# RMP_LED_MODULE.net
KiCad netlist of a schematic drawn in Altium Designer
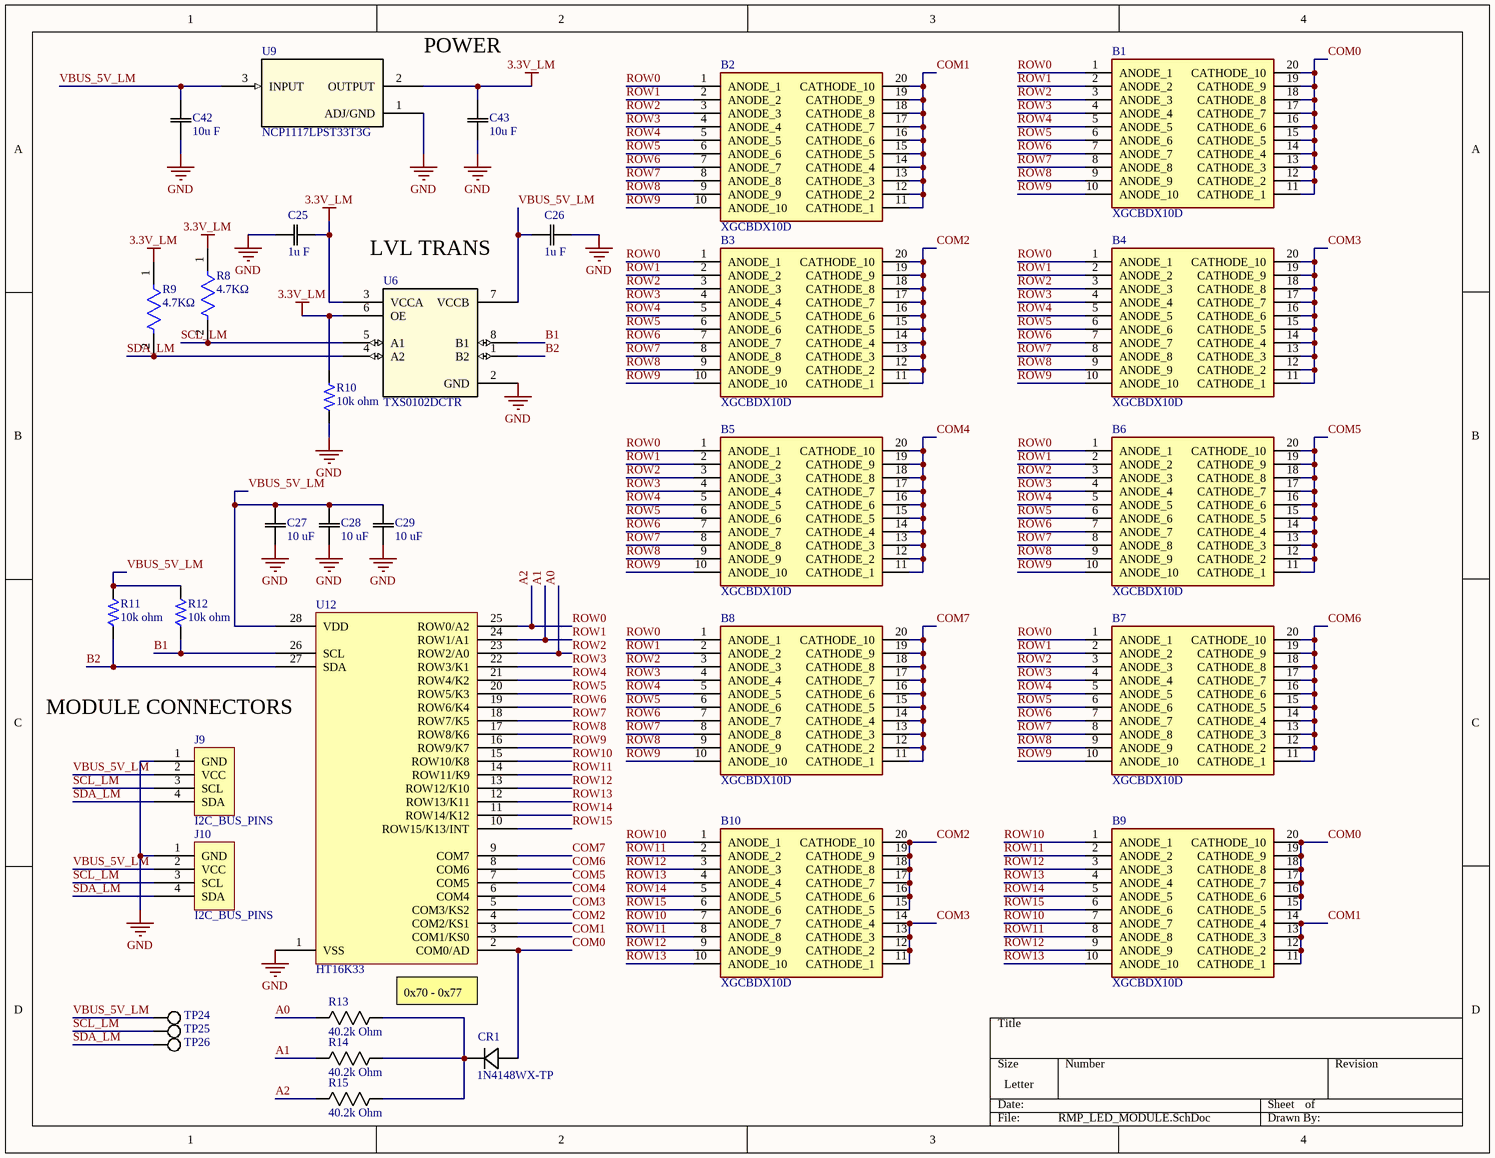
[diagram p0: RMP_LED_MODULE.SchDoc]

(export (version "E")
  (design (tool "Eeschema 10.0.6"))
  (components
    (comp (ref "B1")
      (value "XGCBDX10D")
      (footprint "DIPS750W75P254L2540H825Q20N")
      (description "BARGRAPH 10-SEGMENT BLUE")
      (libsource (lib "Schlib1") (part "XGCBDX10D"))
    )
    (comp (ref "B2")
      (value "XGCBDX10D")
      (footprint "DIPS750W75P254L2540H825Q20N")
      (description "BARGRAPH 10-SEGMENT BLUE")
      (libsource (lib "Schlib1") (part "XGCBDX10D"))
    )
    (comp (ref "B3")
      (value "XGCBDX10D")
      (footprint "DIPS750W75P254L2540H825Q20N")
      (description "BARGRAPH 10-SEGMENT BLUE")
      (libsource (lib "Schlib1") (part "XGCBDX10D"))
    )
    (comp (ref "B4")
      (value "XGCBDX10D")
      (footprint "DIPS750W75P254L2540H825Q20N")
      (description "BARGRAPH 10-SEGMENT BLUE")
      (libsource (lib "Schlib1") (part "XGCBDX10D"))
    )
    (comp (ref "B5")
      (value "XGCBDX10D")
      (footprint "DIPS750W75P254L2540H825Q20N")
      (description "BARGRAPH 10-SEGMENT BLUE")
      (libsource (lib "Schlib1") (part "XGCBDX10D"))
    )
    (comp (ref "B6")
      (value "XGCBDX10D")
      (footprint "DIPS750W75P254L2540H825Q20N")
      (description "BARGRAPH 10-SEGMENT BLUE")
      (libsource (lib "Schlib1") (part "XGCBDX10D"))
    )
    (comp (ref "B7")
      (value "XGCBDX10D")
      (footprint "DIPS750W75P254L2540H825Q20N")
      (description "BARGRAPH 10-SEGMENT BLUE")
      (libsource (lib "Schlib1") (part "XGCBDX10D"))
    )
    (comp (ref "B8")
      (value "XGCBDX10D")
      (footprint "DIPS750W75P254L2540H825Q20N")
      (description "BARGRAPH 10-SEGMENT BLUE")
      (libsource (lib "Schlib1") (part "XGCBDX10D"))
    )
    (comp (ref "B9")
      (value "XGCBDX10D")
      (footprint "DIPS750W75P254L2540H825Q20N")
      (description "BARGRAPH 10-SEGMENT BLUE")
      (libsource (lib "Schlib1") (part "XGCBDX10D"))
    )
    (comp (ref "B10")
      (value "XGCBDX10D")
      (footprint "DIPS750W75P254L2540H825Q20N")
      (description "BARGRAPH 10-SEGMENT BLUE")
      (libsource (lib "Schlib1") (part "XGCBDX10D"))
    )
    (comp (ref "C25")
      (value "1u F")
      (footprint "CAP_CL21B105KAFNNNE_SAM-M")
      (description "1 µF ±10% 25V Ceramic Capacitor X7R 0805 (2012 Metric)")
      (fields (field (name "Comment") "CL21B105KAFNNNE"))
      (libsource (lib "Schlib1") (part "CAP_CL21B105KAFNNNE"))
    )
    (comp (ref "C26")
      (value "1u F")
      (footprint "CAP_CL21B105KAFNNNE_SAM-M")
      (description "1 µF ±10% 25V Ceramic Capacitor X7R 0805 (2012 Metric)")
      (fields (field (name "Comment") "CL21B105KAFNNNE"))
      (libsource (lib "Schlib1") (part "CAP_CL21B105KAFNNNE"))
    )
    (comp (ref "C27")
      (value "10 uF")
      (footprint "CAP_CL21_SAM-M")
      (description "10 µF ±10% 16V Ceramic Capacitor X5R 0805 (2012 Metric)")
      (fields (field (name "Comment") "CL21A106KOQNNNE"))
      (libsource (lib "Schlib1") (part "CAP_CL21A106KOQNNNE"))
    )
    (comp (ref "C28")
      (value "10 uF")
      (footprint "CAP_CL21_SAM-M")
      (description "10 µF ±10% 16V Ceramic Capacitor X5R 0805 (2012 Metric)")
      (fields (field (name "Comment") "CL21A106KOQNNNE"))
      (libsource (lib "Schlib1") (part "CAP_CL21A106KOQNNNE"))
    )
    (comp (ref "C29")
      (value "10 uF")
      (footprint "CAP_CL21_SAM-M")
      (description "10 µF ±10% 16V Ceramic Capacitor X5R 0805 (2012 Metric)")
      (fields (field (name "Comment") "CL21A106KOQNNNE"))
      (libsource (lib "Schlib1") (part "CAP_CL21A106KOQNNNE"))
    )
    (comp (ref "C42")
      (value "10u F")
      (footprint "G-21_MUR-M")
      (description "10 µF ±10% 16V Ceramic Capacitor X5R 0805 (2012 Metric)")
      (fields (field (name "Comment") "GRM21BR61C106KE15K"))
      (libsource (lib "Schlib1") (part "CAP_GRM21BR61C106KE15K"))
    )
    (comp (ref "C43")
      (value "10u F")
      (footprint "G-21_MUR-M")
      (description "10 µF ±10% 16V Ceramic Capacitor X5R 0805 (2012 Metric)")
      (fields (field (name "Comment") "GRM21BR61C106KE15K"))
      (libsource (lib "Schlib1") (part "CAP_GRM21BR61C106KE15K"))
    )
    (comp (ref "CR1")
      (value "1N4148WX-TP")
      (footprint "CR_SOD323_MCC-M")
      (description "No Description Available")
      (libsource (lib "Schlib1") (part "1N4148WX-TP"))
    )
    (comp (ref "J9")
      (value "I2C_BUS_PINS")
      (footprint "4 PIN HEADER")
      (libsource (lib "Schlib1") (part "I2C_BUS_PINS"))
    )
    (comp (ref "J10")
      (value "I2C_BUS_PINS")
      (footprint "4 PIN HEADER")
      (libsource (lib "Schlib1") (part "I2C_BUS_PINS"))
    )
    (comp (ref "R8")
      (value "RT0805FRE134K7L")
      (footprint "FP-RT0805-MFG")
      (description "RT0805 4.7KΩ 0.125W 50 ppm/°C 0.01%")
      (fields
        (field (name "RESISTANCE") "4.7KΩ")
        (field (name "TOLERANCE") "0.0001")
        (field (name "MANUFACTURER") "Yageo")
      )
      (libsource (lib "Altium Content Vault") (part "1029c3af85768c4190bb7ad29bc67b5"))
    )
    (comp (ref "R9")
      (value "RT0805FRE134K7L")
      (footprint "FP-RT0805-MFG")
      (description "RT0805 4.7KΩ 0.125W 50 ppm/°C 0.01%")
      (fields
        (field (name "RESISTANCE") "4.7KΩ")
        (field (name "TOLERANCE") "0.0001")
        (field (name "MANUFACTURER") "Yageo")
      )
      (libsource (lib "Altium Content Vault") (part "1029c3af85768c4190bb7ad29bc67b5"))
    )
    (comp (ref "R10")
      (value "10k ohm")
      (footprint "STA_RNCP0805_STP-M")
      (description "10 kOhms ±1% 0.25W, 1/4W Chip Resistor 0805 (2012 Metric) Anti-Sulfur Thin Film")
      (fields (field (name "Comment") "RNCP0805FTD10K0"))
      (libsource (lib "Schlib1") (part "RES_RNCP0805FTD10K0"))
    )
    (comp (ref "R11")
      (value "10k ohm")
      (footprint "STA_RNCP0805_STP-M")
      (description "10 kOhms ±1% 0.25W, 1/4W Chip Resistor 0805 (2012 Metric) Anti-Sulfur Thin Film")
      (fields (field (name "Comment") "RNCP0805FTD10K0"))
      (libsource (lib "Schlib1") (part "RES_RNCP0805FTD10K0"))
    )
    (comp (ref "R12")
      (value "10k ohm")
      (footprint "STA_RNCP0805_STP-M")
      (description "10 kOhms ±1% 0.25W, 1/4W Chip Resistor 0805 (2012 Metric) Anti-Sulfur Thin Film")
      (fields (field (name "Comment") "RNCP0805FTD10K0"))
      (libsource (lib "Schlib1") (part "RES_RNCP0805FTD10K0"))
    )
    (comp (ref "R13")
      (value "40.2k Ohm")
      (footprint "STA_RNCP0805_STP-M - duplicate")
      (description "40.2 kOhms ±1% 0.25W, 1/4W Chip Resistor 0805 (2012 Metric) Anti-Sulfur Thin Film")
      (fields (field (name "Comment") "RNCP0805FTD40K2"))
      (libsource (lib "Schlib1") (part "RES_RNCP0805FTD40K2"))
    )
    (comp (ref "R14")
      (value "40.2k Ohm")
      (footprint "STA_RNCP0805_STP-M - duplicate")
      (description "40.2 kOhms ±1% 0.25W, 1/4W Chip Resistor 0805 (2012 Metric) Anti-Sulfur Thin Film")
      (fields (field (name "Comment") "RNCP0805FTD40K2"))
      (libsource (lib "Schlib1") (part "RES_RNCP0805FTD40K2"))
    )
    (comp (ref "R15")
      (value "40.2k Ohm")
      (footprint "STA_RNCP0805_STP-M - duplicate")
      (description "40.2 kOhms ±1% 0.25W, 1/4W Chip Resistor 0805 (2012 Metric) Anti-Sulfur Thin Film")
      (fields (field (name "Comment") "RNCP0805FTD40K2"))
      (libsource (lib "Schlib1") (part "RES_RNCP0805FTD40K2"))
    )
    (comp (ref "TP24")
      (value "TestPoint")
      (footprint "Testpoint")
      (libsource (lib "Schlib1") (part "TestPoint"))
    )
    (comp (ref "TP25")
      (value "TestPoint")
      (footprint "Testpoint")
      (libsource (lib "Schlib1") (part "TestPoint"))
    )
    (comp (ref "TP26")
      (value "TestPoint")
      (footprint "Testpoint")
      (libsource (lib "Schlib1") (part "TestPoint"))
    )
    (comp (ref "U6")
      (value "TXS0102DCTR")
      (footprint "DCT8")
      (description "Voltage Level Translator Bidirectional 1 Circuit 2 Channel 24Mbps SM8")
      (libsource (lib "Schlib1") (part "TXS0102DCTR"))
    )
    (comp (ref "U9")
      (value "NCP1117LPST33T3G")
      (footprint "SOT223-3_ONS-M")
      (description "Linear Voltage Regulator IC Positive Fixed 1 Output 1A SOT-223")
      (libsource (lib "Schlib1") (part "NCP1117LPST33T3G"))
    )
    (comp (ref "U12")
      (value "HT16K33")
      (footprint "SOP-28-300mil")
      (description "16X8 LED MAtrix Driver")
      (libsource (lib "Schlib1") (part "HT16K33"))
    )
  )
  (nets
    (net (code "1") (name "/A0") (class "Default")
      (node (ref "B1") (pin "3") (pinfunction "ANODE_3_3") (pintype "passive"))
      (node (ref "B2") (pin "3") (pinfunction "ANODE_3_3") (pintype "passive"))
      (node (ref "B3") (pin "3") (pinfunction "ANODE_3_3") (pintype "passive"))
      (node (ref "B4") (pin "3") (pinfunction "ANODE_3_3") (pintype "passive"))
      (node (ref "B5") (pin "3") (pinfunction "ANODE_3_3") (pintype "passive"))
      (node (ref "B6") (pin "3") (pinfunction "ANODE_3_3") (pintype "passive"))
      (node (ref "B7") (pin "3") (pinfunction "ANODE_3_3") (pintype "passive"))
      (node (ref "B8") (pin "3") (pinfunction "ANODE_3_3") (pintype "passive"))
      (node (ref "R13") (pin "2") (pinfunction "2_2") (pintype "passive"))
      (node (ref "U12") (pin "23") (pinfunction "ROW2/A0_23") (pintype "passive"))
    )
    (net (code "2") (name "/A1") (class "Default")
      (node (ref "B1") (pin "2") (pinfunction "ANODE_2_2") (pintype "passive"))
      (node (ref "B2") (pin "2") (pinfunction "ANODE_2_2") (pintype "passive"))
      (node (ref "B3") (pin "2") (pinfunction "ANODE_2_2") (pintype "passive"))
      (node (ref "B4") (pin "2") (pinfunction "ANODE_2_2") (pintype "passive"))
      (node (ref "B5") (pin "2") (pinfunction "ANODE_2_2") (pintype "passive"))
      (node (ref "B6") (pin "2") (pinfunction "ANODE_2_2") (pintype "passive"))
      (node (ref "B7") (pin "2") (pinfunction "ANODE_2_2") (pintype "passive"))
      (node (ref "B8") (pin "2") (pinfunction "ANODE_2_2") (pintype "passive"))
      (node (ref "R14") (pin "2") (pinfunction "2_2") (pintype "passive"))
      (node (ref "U12") (pin "24") (pinfunction "ROW1/A1_24") (pintype "passive"))
    )
    (net (code "3") (name "/A2") (class "Default")
      (node (ref "B1") (pin "1") (pinfunction "ANODE_1_1") (pintype "passive"))
      (node (ref "B2") (pin "1") (pinfunction "ANODE_1_1") (pintype "passive"))
      (node (ref "B3") (pin "1") (pinfunction "ANODE_1_1") (pintype "passive"))
      (node (ref "B4") (pin "1") (pinfunction "ANODE_1_1") (pintype "passive"))
      (node (ref "B5") (pin "1") (pinfunction "ANODE_1_1") (pintype "passive"))
      (node (ref "B6") (pin "1") (pinfunction "ANODE_1_1") (pintype "passive"))
      (node (ref "B7") (pin "1") (pinfunction "ANODE_1_1") (pintype "passive"))
      (node (ref "B8") (pin "1") (pinfunction "ANODE_1_1") (pintype "passive"))
      (node (ref "R15") (pin "2") (pinfunction "2_2") (pintype "passive"))
      (node (ref "U12") (pin "25") (pinfunction "ROW0/A2_25") (pintype "passive"))
    )
    (net (code "4") (name "/B1") (class "Default")
      (node (ref "R12") (pin "1") (pinfunction "1_1") (pintype "passive"))
      (node (ref "U12") (pin "26") (pinfunction "SCL_26") (pintype "passive"))
      (node (ref "U6") (pin "8") (pinfunction "B1_8") (pintype "bidirectional"))
    )
    (net (code "5") (name "/B2") (class "Default")
      (node (ref "R11") (pin "1") (pinfunction "1_1") (pintype "passive"))
      (node (ref "U12") (pin "27") (pinfunction "SDA_27") (pintype "passive"))
      (node (ref "U6") (pin "1") (pinfunction "B2_1") (pintype "bidirectional"))
    )
    (net (code "6") (name "/COM0") (class "Default")
      (node (ref "B1") (pin "11") (pinfunction "CATHODE_1_11") (pintype "passive"))
      (node (ref "B1") (pin "12") (pinfunction "CATHODE_2_12") (pintype "passive"))
      (node (ref "B1") (pin "13") (pinfunction "CATHODE_3_13") (pintype "passive"))
      (node (ref "B1") (pin "14") (pinfunction "CATHODE_4_14") (pintype "passive"))
      (node (ref "B1") (pin "15") (pinfunction "CATHODE_5_15") (pintype "passive"))
      (node (ref "B1") (pin "16") (pinfunction "CATHODE_6_16") (pintype "passive"))
      (node (ref "B1") (pin "17") (pinfunction "CATHODE_7_17") (pintype "passive"))
      (node (ref "B1") (pin "18") (pinfunction "CATHODE_8_18") (pintype "passive"))
      (node (ref "B1") (pin "19") (pinfunction "CATHODE_9_19") (pintype "passive"))
      (node (ref "B1") (pin "20") (pinfunction "CATHODE_10_20") (pintype "passive"))
      (node (ref "B9") (pin "15") (pinfunction "CATHODE_5_15") (pintype "passive"))
      (node (ref "B9") (pin "16") (pinfunction "CATHODE_6_16") (pintype "passive"))
      (node (ref "B9") (pin "17") (pinfunction "CATHODE_7_17") (pintype "passive"))
      (node (ref "B9") (pin "18") (pinfunction "CATHODE_8_18") (pintype "passive"))
      (node (ref "B9") (pin "19") (pinfunction "CATHODE_9_19") (pintype "passive"))
      (node (ref "B9") (pin "20") (pinfunction "CATHODE_10_20") (pintype "passive"))
      (node (ref "CR1") (pin "2") (pinfunction "2_2") (pintype "passive"))
      (node (ref "U12") (pin "2") (pinfunction "COM0/AD_2") (pintype "passive"))
    )
    (net (code "7") (name "/COM1") (class "Default")
      (node (ref "B2") (pin "11") (pinfunction "CATHODE_1_11") (pintype "passive"))
      (node (ref "B2") (pin "12") (pinfunction "CATHODE_2_12") (pintype "passive"))
      (node (ref "B2") (pin "13") (pinfunction "CATHODE_3_13") (pintype "passive"))
      (node (ref "B2") (pin "14") (pinfunction "CATHODE_4_14") (pintype "passive"))
      (node (ref "B2") (pin "15") (pinfunction "CATHODE_5_15") (pintype "passive"))
      (node (ref "B2") (pin "16") (pinfunction "CATHODE_6_16") (pintype "passive"))
      (node (ref "B2") (pin "17") (pinfunction "CATHODE_7_17") (pintype "passive"))
      (node (ref "B2") (pin "18") (pinfunction "CATHODE_8_18") (pintype "passive"))
      (node (ref "B2") (pin "19") (pinfunction "CATHODE_9_19") (pintype "passive"))
      (node (ref "B2") (pin "20") (pinfunction "CATHODE_10_20") (pintype "passive"))
      (node (ref "B9") (pin "11") (pinfunction "CATHODE_1_11") (pintype "passive"))
      (node (ref "B9") (pin "12") (pinfunction "CATHODE_2_12") (pintype "passive"))
      (node (ref "B9") (pin "13") (pinfunction "CATHODE_3_13") (pintype "passive"))
      (node (ref "B9") (pin "14") (pinfunction "CATHODE_4_14") (pintype "passive"))
      (node (ref "U12") (pin "3") (pinfunction "COM1/KS0_3") (pintype "passive"))
    )
    (net (code "8") (name "/COM2") (class "Default")
      (node (ref "B10") (pin "15") (pinfunction "CATHODE_5_15") (pintype "passive"))
      (node (ref "B10") (pin "16") (pinfunction "CATHODE_6_16") (pintype "passive"))
      (node (ref "B10") (pin "17") (pinfunction "CATHODE_7_17") (pintype "passive"))
      (node (ref "B10") (pin "18") (pinfunction "CATHODE_8_18") (pintype "passive"))
      (node (ref "B10") (pin "19") (pinfunction "CATHODE_9_19") (pintype "passive"))
      (node (ref "B10") (pin "20") (pinfunction "CATHODE_10_20") (pintype "passive"))
      (node (ref "B3") (pin "11") (pinfunction "CATHODE_1_11") (pintype "passive"))
      (node (ref "B3") (pin "12") (pinfunction "CATHODE_2_12") (pintype "passive"))
      (node (ref "B3") (pin "13") (pinfunction "CATHODE_3_13") (pintype "passive"))
      (node (ref "B3") (pin "14") (pinfunction "CATHODE_4_14") (pintype "passive"))
      (node (ref "B3") (pin "15") (pinfunction "CATHODE_5_15") (pintype "passive"))
      (node (ref "B3") (pin "16") (pinfunction "CATHODE_6_16") (pintype "passive"))
      (node (ref "B3") (pin "17") (pinfunction "CATHODE_7_17") (pintype "passive"))
      (node (ref "B3") (pin "18") (pinfunction "CATHODE_8_18") (pintype "passive"))
      (node (ref "B3") (pin "19") (pinfunction "CATHODE_9_19") (pintype "passive"))
      (node (ref "B3") (pin "20") (pinfunction "CATHODE_10_20") (pintype "passive"))
      (node (ref "U12") (pin "4") (pinfunction "COM2/KS1_4") (pintype "passive"))
    )
    (net (code "9") (name "/COM3") (class "Default")
      (node (ref "B10") (pin "11") (pinfunction "CATHODE_1_11") (pintype "passive"))
      (node (ref "B10") (pin "12") (pinfunction "CATHODE_2_12") (pintype "passive"))
      (node (ref "B10") (pin "13") (pinfunction "CATHODE_3_13") (pintype "passive"))
      (node (ref "B10") (pin "14") (pinfunction "CATHODE_4_14") (pintype "passive"))
      (node (ref "B4") (pin "11") (pinfunction "CATHODE_1_11") (pintype "passive"))
      (node (ref "B4") (pin "12") (pinfunction "CATHODE_2_12") (pintype "passive"))
      (node (ref "B4") (pin "13") (pinfunction "CATHODE_3_13") (pintype "passive"))
      (node (ref "B4") (pin "14") (pinfunction "CATHODE_4_14") (pintype "passive"))
      (node (ref "B4") (pin "15") (pinfunction "CATHODE_5_15") (pintype "passive"))
      (node (ref "B4") (pin "16") (pinfunction "CATHODE_6_16") (pintype "passive"))
      (node (ref "B4") (pin "17") (pinfunction "CATHODE_7_17") (pintype "passive"))
      (node (ref "B4") (pin "18") (pinfunction "CATHODE_8_18") (pintype "passive"))
      (node (ref "B4") (pin "19") (pinfunction "CATHODE_9_19") (pintype "passive"))
      (node (ref "B4") (pin "20") (pinfunction "CATHODE_10_20") (pintype "passive"))
      (node (ref "U12") (pin "5") (pinfunction "COM3/KS2_5") (pintype "passive"))
    )
    (net (code "10") (name "/COM4") (class "Default")
      (node (ref "B5") (pin "11") (pinfunction "CATHODE_1_11") (pintype "passive"))
      (node (ref "B5") (pin "12") (pinfunction "CATHODE_2_12") (pintype "passive"))
      (node (ref "B5") (pin "13") (pinfunction "CATHODE_3_13") (pintype "passive"))
      (node (ref "B5") (pin "14") (pinfunction "CATHODE_4_14") (pintype "passive"))
      (node (ref "B5") (pin "15") (pinfunction "CATHODE_5_15") (pintype "passive"))
      (node (ref "B5") (pin "16") (pinfunction "CATHODE_6_16") (pintype "passive"))
      (node (ref "B5") (pin "17") (pinfunction "CATHODE_7_17") (pintype "passive"))
      (node (ref "B5") (pin "18") (pinfunction "CATHODE_8_18") (pintype "passive"))
      (node (ref "B5") (pin "19") (pinfunction "CATHODE_9_19") (pintype "passive"))
      (node (ref "B5") (pin "20") (pinfunction "CATHODE_10_20") (pintype "passive"))
      (node (ref "U12") (pin "6") (pinfunction "COM4_6") (pintype "passive"))
    )
    (net (code "11") (name "/COM5") (class "Default")
      (node (ref "B6") (pin "11") (pinfunction "CATHODE_1_11") (pintype "passive"))
      (node (ref "B6") (pin "12") (pinfunction "CATHODE_2_12") (pintype "passive"))
      (node (ref "B6") (pin "13") (pinfunction "CATHODE_3_13") (pintype "passive"))
      (node (ref "B6") (pin "14") (pinfunction "CATHODE_4_14") (pintype "passive"))
      (node (ref "B6") (pin "15") (pinfunction "CATHODE_5_15") (pintype "passive"))
      (node (ref "B6") (pin "16") (pinfunction "CATHODE_6_16") (pintype "passive"))
      (node (ref "B6") (pin "17") (pinfunction "CATHODE_7_17") (pintype "passive"))
      (node (ref "B6") (pin "18") (pinfunction "CATHODE_8_18") (pintype "passive"))
      (node (ref "B6") (pin "19") (pinfunction "CATHODE_9_19") (pintype "passive"))
      (node (ref "B6") (pin "20") (pinfunction "CATHODE_10_20") (pintype "passive"))
      (node (ref "U12") (pin "7") (pinfunction "COM5_7") (pintype "passive"))
    )
    (net (code "12") (name "/COM6") (class "Default")
      (node (ref "B7") (pin "11") (pinfunction "CATHODE_1_11") (pintype "passive"))
      (node (ref "B7") (pin "12") (pinfunction "CATHODE_2_12") (pintype "passive"))
      (node (ref "B7") (pin "13") (pinfunction "CATHODE_3_13") (pintype "passive"))
      (node (ref "B7") (pin "14") (pinfunction "CATHODE_4_14") (pintype "passive"))
      (node (ref "B7") (pin "15") (pinfunction "CATHODE_5_15") (pintype "passive"))
      (node (ref "B7") (pin "16") (pinfunction "CATHODE_6_16") (pintype "passive"))
      (node (ref "B7") (pin "17") (pinfunction "CATHODE_7_17") (pintype "passive"))
      (node (ref "B7") (pin "18") (pinfunction "CATHODE_8_18") (pintype "passive"))
      (node (ref "B7") (pin "19") (pinfunction "CATHODE_9_19") (pintype "passive"))
      (node (ref "B7") (pin "20") (pinfunction "CATHODE_10_20") (pintype "passive"))
      (node (ref "U12") (pin "8") (pinfunction "COM6_8") (pintype "passive"))
    )
    (net (code "13") (name "/COM7") (class "Default")
      (node (ref "B8") (pin "11") (pinfunction "CATHODE_1_11") (pintype "passive"))
      (node (ref "B8") (pin "12") (pinfunction "CATHODE_2_12") (pintype "passive"))
      (node (ref "B8") (pin "13") (pinfunction "CATHODE_3_13") (pintype "passive"))
      (node (ref "B8") (pin "14") (pinfunction "CATHODE_4_14") (pintype "passive"))
      (node (ref "B8") (pin "15") (pinfunction "CATHODE_5_15") (pintype "passive"))
      (node (ref "B8") (pin "16") (pinfunction "CATHODE_6_16") (pintype "passive"))
      (node (ref "B8") (pin "17") (pinfunction "CATHODE_7_17") (pintype "passive"))
      (node (ref "B8") (pin "18") (pinfunction "CATHODE_8_18") (pintype "passive"))
      (node (ref "B8") (pin "19") (pinfunction "CATHODE_9_19") (pintype "passive"))
      (node (ref "B8") (pin "20") (pinfunction "CATHODE_10_20") (pintype "passive"))
      (node (ref "U12") (pin "9") (pinfunction "COM7_9") (pintype "passive"))
    )
    (net (code "14") (name "/ROW3") (class "Default")
      (node (ref "B1") (pin "4") (pinfunction "ANODE_4_4") (pintype "passive"))
      (node (ref "B2") (pin "4") (pinfunction "ANODE_4_4") (pintype "passive"))
      (node (ref "B3") (pin "4") (pinfunction "ANODE_4_4") (pintype "passive"))
      (node (ref "B4") (pin "4") (pinfunction "ANODE_4_4") (pintype "passive"))
      (node (ref "B5") (pin "4") (pinfunction "ANODE_4_4") (pintype "passive"))
      (node (ref "B6") (pin "4") (pinfunction "ANODE_4_4") (pintype "passive"))
      (node (ref "B7") (pin "4") (pinfunction "ANODE_4_4") (pintype "passive"))
      (node (ref "B8") (pin "4") (pinfunction "ANODE_4_4") (pintype "passive"))
      (node (ref "U12") (pin "22") (pinfunction "ROW3/K1_22") (pintype "passive"))
    )
    (net (code "15") (name "/ROW4") (class "Default")
      (node (ref "B1") (pin "5") (pinfunction "ANODE_5_5") (pintype "passive"))
      (node (ref "B2") (pin "5") (pinfunction "ANODE_5_5") (pintype "passive"))
      (node (ref "B3") (pin "5") (pinfunction "ANODE_5_5") (pintype "passive"))
      (node (ref "B4") (pin "5") (pinfunction "ANODE_5_5") (pintype "passive"))
      (node (ref "B5") (pin "5") (pinfunction "ANODE_5_5") (pintype "passive"))
      (node (ref "B6") (pin "5") (pinfunction "ANODE_5_5") (pintype "passive"))
      (node (ref "B7") (pin "5") (pinfunction "ANODE_5_5") (pintype "passive"))
      (node (ref "B8") (pin "5") (pinfunction "ANODE_5_5") (pintype "passive"))
      (node (ref "U12") (pin "21") (pinfunction "ROW4/K2_21") (pintype "passive"))
    )
    (net (code "16") (name "/ROW5") (class "Default")
      (node (ref "B1") (pin "6") (pinfunction "ANODE_6_6") (pintype "passive"))
      (node (ref "B2") (pin "6") (pinfunction "ANODE_6_6") (pintype "passive"))
      (node (ref "B3") (pin "6") (pinfunction "ANODE_6_6") (pintype "passive"))
      (node (ref "B4") (pin "6") (pinfunction "ANODE_6_6") (pintype "passive"))
      (node (ref "B5") (pin "6") (pinfunction "ANODE_6_6") (pintype "passive"))
      (node (ref "B6") (pin "6") (pinfunction "ANODE_6_6") (pintype "passive"))
      (node (ref "B7") (pin "6") (pinfunction "ANODE_6_6") (pintype "passive"))
      (node (ref "B8") (pin "6") (pinfunction "ANODE_6_6") (pintype "passive"))
      (node (ref "U12") (pin "20") (pinfunction "ROW5/K3_20") (pintype "passive"))
    )
    (net (code "17") (name "/ROW6") (class "Default")
      (node (ref "B1") (pin "7") (pinfunction "ANODE_7_7") (pintype "passive"))
      (node (ref "B2") (pin "7") (pinfunction "ANODE_7_7") (pintype "passive"))
      (node (ref "B3") (pin "7") (pinfunction "ANODE_7_7") (pintype "passive"))
      (node (ref "B4") (pin "7") (pinfunction "ANODE_7_7") (pintype "passive"))
      (node (ref "B5") (pin "7") (pinfunction "ANODE_7_7") (pintype "passive"))
      (node (ref "B6") (pin "7") (pinfunction "ANODE_7_7") (pintype "passive"))
      (node (ref "B7") (pin "7") (pinfunction "ANODE_7_7") (pintype "passive"))
      (node (ref "B8") (pin "7") (pinfunction "ANODE_7_7") (pintype "passive"))
      (node (ref "U12") (pin "19") (pinfunction "ROW6/K4_19") (pintype "passive"))
    )
    (net (code "18") (name "/ROW7") (class "Default")
      (node (ref "B1") (pin "8") (pinfunction "ANODE_8_8") (pintype "passive"))
      (node (ref "B2") (pin "8") (pinfunction "ANODE_8_8") (pintype "passive"))
      (node (ref "B3") (pin "8") (pinfunction "ANODE_8_8") (pintype "passive"))
      (node (ref "B4") (pin "8") (pinfunction "ANODE_8_8") (pintype "passive"))
      (node (ref "B5") (pin "8") (pinfunction "ANODE_8_8") (pintype "passive"))
      (node (ref "B6") (pin "8") (pinfunction "ANODE_8_8") (pintype "passive"))
      (node (ref "B7") (pin "8") (pinfunction "ANODE_8_8") (pintype "passive"))
      (node (ref "B8") (pin "8") (pinfunction "ANODE_8_8") (pintype "passive"))
      (node (ref "U12") (pin "18") (pinfunction "ROW7/K5_18") (pintype "passive"))
    )
    (net (code "19") (name "/ROW8") (class "Default")
      (node (ref "B1") (pin "9") (pinfunction "ANODE_9_9") (pintype "passive"))
      (node (ref "B2") (pin "9") (pinfunction "ANODE_9_9") (pintype "passive"))
      (node (ref "B3") (pin "9") (pinfunction "ANODE_9_9") (pintype "passive"))
      (node (ref "B4") (pin "9") (pinfunction "ANODE_9_9") (pintype "passive"))
      (node (ref "B5") (pin "9") (pinfunction "ANODE_9_9") (pintype "passive"))
      (node (ref "B6") (pin "9") (pinfunction "ANODE_9_9") (pintype "passive"))
      (node (ref "B7") (pin "9") (pinfunction "ANODE_9_9") (pintype "passive"))
      (node (ref "B8") (pin "9") (pinfunction "ANODE_9_9") (pintype "passive"))
      (node (ref "U12") (pin "17") (pinfunction "ROW8/K6_17") (pintype "passive"))
    )
    (net (code "20") (name "/ROW9") (class "Default")
      (node (ref "B1") (pin "10") (pinfunction "ANODE_10_10") (pintype "passive"))
      (node (ref "B2") (pin "10") (pinfunction "ANODE_10_10") (pintype "passive"))
      (node (ref "B3") (pin "10") (pinfunction "ANODE_10_10") (pintype "passive"))
      (node (ref "B4") (pin "10") (pinfunction "ANODE_10_10") (pintype "passive"))
      (node (ref "B5") (pin "10") (pinfunction "ANODE_10_10") (pintype "passive"))
      (node (ref "B6") (pin "10") (pinfunction "ANODE_10_10") (pintype "passive"))
      (node (ref "B7") (pin "10") (pinfunction "ANODE_10_10") (pintype "passive"))
      (node (ref "B8") (pin "10") (pinfunction "ANODE_10_10") (pintype "passive"))
      (node (ref "U12") (pin "16") (pinfunction "ROW9/K7_16") (pintype "passive"))
    )
    (net (code "21") (name "/ROW10") (class "Default")
      (node (ref "B10") (pin "1") (pinfunction "ANODE_1_1") (pintype "passive"))
      (node (ref "B10") (pin "7") (pinfunction "ANODE_7_7") (pintype "passive"))
      (node (ref "B9") (pin "1") (pinfunction "ANODE_1_1") (pintype "passive"))
      (node (ref "B9") (pin "7") (pinfunction "ANODE_7_7") (pintype "passive"))
      (node (ref "U12") (pin "15") (pinfunction "ROW10/K8_15") (pintype "passive"))
    )
    (net (code "22") (name "/ROW11") (class "Default")
      (node (ref "B10") (pin "2") (pinfunction "ANODE_2_2") (pintype "passive"))
      (node (ref "B10") (pin "8") (pinfunction "ANODE_8_8") (pintype "passive"))
      (node (ref "B9") (pin "2") (pinfunction "ANODE_2_2") (pintype "passive"))
      (node (ref "B9") (pin "8") (pinfunction "ANODE_8_8") (pintype "passive"))
      (node (ref "U12") (pin "14") (pinfunction "ROW11/K9_14") (pintype "passive"))
    )
    (net (code "23") (name "/ROW12") (class "Default")
      (node (ref "B10") (pin "3") (pinfunction "ANODE_3_3") (pintype "passive"))
      (node (ref "B10") (pin "9") (pinfunction "ANODE_9_9") (pintype "passive"))
      (node (ref "B9") (pin "3") (pinfunction "ANODE_3_3") (pintype "passive"))
      (node (ref "B9") (pin "9") (pinfunction "ANODE_9_9") (pintype "passive"))
      (node (ref "U12") (pin "13") (pinfunction "ROW12/K10_13") (pintype "passive"))
    )
    (net (code "24") (name "/ROW13") (class "Default")
      (node (ref "B10") (pin "10") (pinfunction "ANODE_10_10") (pintype "passive"))
      (node (ref "B10") (pin "4") (pinfunction "ANODE_4_4") (pintype "passive"))
      (node (ref "B9") (pin "10") (pinfunction "ANODE_10_10") (pintype "passive"))
      (node (ref "B9") (pin "4") (pinfunction "ANODE_4_4") (pintype "passive"))
      (node (ref "U12") (pin "12") (pinfunction "ROW13/K11_12") (pintype "passive"))
    )
    (net (code "25") (name "/ROW14") (class "Default")
      (node (ref "B10") (pin "5") (pinfunction "ANODE_5_5") (pintype "passive"))
      (node (ref "B9") (pin "5") (pinfunction "ANODE_5_5") (pintype "passive"))
      (node (ref "U12") (pin "11") (pinfunction "ROW14/K12_11") (pintype "passive"))
    )
    (net (code "26") (name "/ROW15") (class "Default")
      (node (ref "B10") (pin "6") (pinfunction "ANODE_6_6") (pintype "passive"))
      (node (ref "B9") (pin "6") (pinfunction "ANODE_6_6") (pintype "passive"))
      (node (ref "U12") (pin "10") (pinfunction "ROW15/K13/INT_10") (pintype "passive"))
    )
    (net (code "27") (name "/SCL_LM") (class "Default")
      (node (ref "J10") (pin "3") (pinfunction "SCL_3") (pintype "passive"))
      (node (ref "J9") (pin "3") (pinfunction "SCL_3") (pintype "passive"))
      (node (ref "R8") (pin "2") (pinfunction "2_2") (pintype "passive"))
      (node (ref "TP25") (pin "1") (pinfunction "1_1") (pintype "passive"))
      (node (ref "U6") (pin "5") (pinfunction "A1_5") (pintype "bidirectional"))
    )
    (net (code "28") (name "/SDA_LM") (class "Default")
      (node (ref "J10") (pin "4") (pinfunction "SDA_4") (pintype "passive"))
      (node (ref "J9") (pin "4") (pinfunction "SDA_4") (pintype "passive"))
      (node (ref "R9") (pin "2") (pinfunction "2_2") (pintype "passive"))
      (node (ref "TP26") (pin "1") (pinfunction "1_1") (pintype "passive"))
      (node (ref "U6") (pin "4") (pinfunction "A2_4") (pintype "bidirectional"))
    )
    (net (code "29") (name "/VBUS_5V_LM") (class "Default")
      (node (ref "C26") (pin "2") (pinfunction "2_2") (pintype "passive"))
      (node (ref "C27") (pin "2") (pinfunction "2_2") (pintype "passive"))
      (node (ref "C28") (pin "2") (pinfunction "2_2") (pintype "passive"))
      (node (ref "C29") (pin "2") (pinfunction "2_2") (pintype "passive"))
      (node (ref "C42") (pin "2") (pinfunction "2_2") (pintype "passive"))
      (node (ref "J10") (pin "2") (pinfunction "VCC_2") (pintype "passive"))
      (node (ref "J9") (pin "2") (pinfunction "VCC_2") (pintype "passive"))
      (node (ref "R11") (pin "2") (pinfunction "2_2") (pintype "passive"))
      (node (ref "R12") (pin "2") (pinfunction "2_2") (pintype "passive"))
      (node (ref "TP24") (pin "1") (pinfunction "1_1") (pintype "passive"))
      (node (ref "U12") (pin "28") (pinfunction "VDD_28") (pintype "passive"))
      (node (ref "U6") (pin "7") (pinfunction "VCCB_7") (pintype "power_in"))
      (node (ref "U9") (pin "3") (pinfunction "INPUT_3") (pintype "input"))
    )
    (net (code "30") (name "3.3V_LM") (class "Default")
      (node (ref "C25") (pin "1") (pinfunction "1_1") (pintype "passive"))
      (node (ref "C43") (pin "2") (pinfunction "2_2") (pintype "passive"))
      (node (ref "R10") (pin "1") (pinfunction "1_1") (pintype "passive"))
      (node (ref "R8") (pin "1") (pinfunction "1_1") (pintype "passive"))
      (node (ref "R9") (pin "1") (pinfunction "1_1") (pintype "passive"))
      (node (ref "U6") (pin "3") (pinfunction "VCCA_3") (pintype "power_in"))
      (node (ref "U6") (pin "6") (pinfunction "OE_6") (pintype "power_in"))
      (node (ref "U9") (pin "2") (pinfunction "OUTPUT_2") (pintype "power_in"))
    )
    (net (code "31") (name "GND") (class "Default")
      (node (ref "C25") (pin "2") (pinfunction "2_2") (pintype "passive"))
      (node (ref "C26") (pin "1") (pinfunction "1_1") (pintype "passive"))
      (node (ref "C27") (pin "1") (pinfunction "1_1") (pintype "passive"))
      (node (ref "C28") (pin "1") (pinfunction "1_1") (pintype "passive"))
      (node (ref "C29") (pin "1") (pinfunction "1_1") (pintype "passive"))
      (node (ref "C42") (pin "1") (pinfunction "1_1") (pintype "passive"))
      (node (ref "C43") (pin "1") (pinfunction "1_1") (pintype "passive"))
      (node (ref "J10") (pin "1") (pinfunction "GND_1") (pintype "passive"))
      (node (ref "J9") (pin "1") (pinfunction "GND_1") (pintype "passive"))
      (node (ref "R10") (pin "2") (pinfunction "2_2") (pintype "passive"))
      (node (ref "U12") (pin "1") (pinfunction "VSS_1") (pintype "passive"))
      (node (ref "U6") (pin "2") (pinfunction "GND_2") (pintype "power_in"))
      (node (ref "U9") (pin "1") (pinfunction "ADJ/GND_1") (pintype "power_in"))
    )
    (net (code "32") (name "Net-(CR1-Pad1)") (class "Default")
      (node (ref "CR1") (pin "1") (pinfunction "1_1") (pintype "passive"))
      (node (ref "R13") (pin "1") (pinfunction "1_1") (pintype "passive"))
      (node (ref "R14") (pin "1") (pinfunction "1_1") (pintype "passive"))
      (node (ref "R15") (pin "1") (pinfunction "1_1") (pintype "passive"))
    )
  )
)
